# TapuinoMini.net
KiCad netlist of a schematic drawn in EAGLE
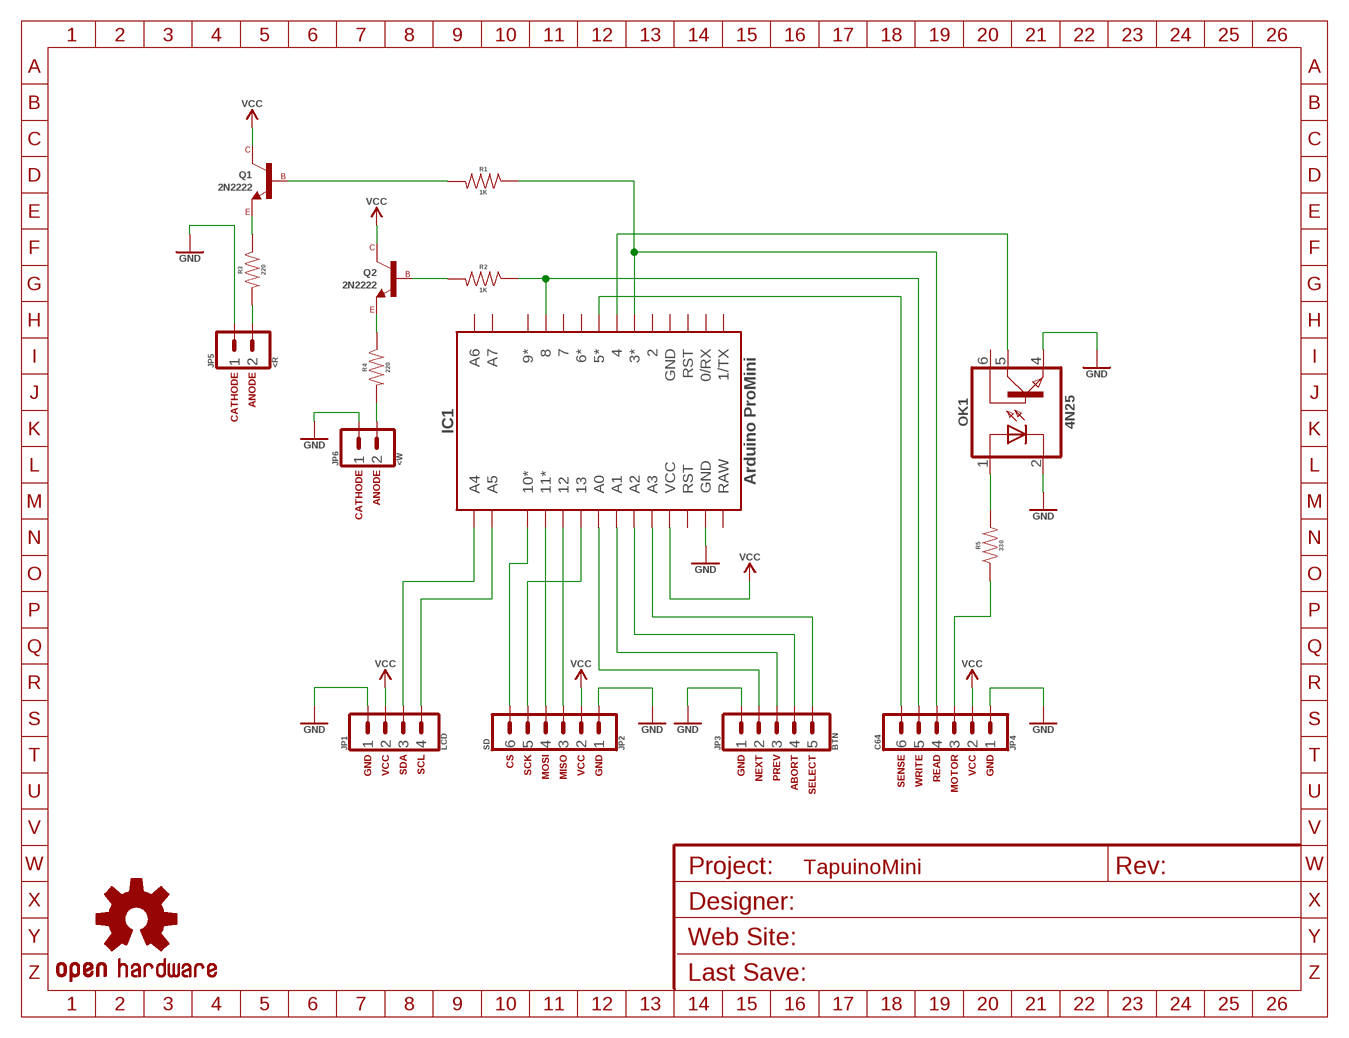
[diagram p0: schematic, sheet 1]

(export (version "E")
  (design (tool "Eeschema 10.0.6"))
  (components
    (comp (ref "IC1")
      (value "Arduino ProMini")
      (footprint "eagle-import:PROMINI_A")
      (libsource (lib "eagle-import") (part "PROMINI_A"))
    )
    (comp (ref "JP1")
      (value "LCD")
      (footprint "eagle-import:1X04_SQR")
      (libsource (lib "eagle-import") (part "1X04_SQR"))
    )
    (comp (ref "JP2")
      (value "SD")
      (footprint "eagle-import:1X06_SQR")
      (libsource (lib "eagle-import") (part "1X06_SQR"))
    )
    (comp (ref "JP3")
      (value "BTN")
      (footprint "eagle-import:1X05_SQR")
      (libsource (lib "eagle-import") (part "1X05_SQR"))
    )
    (comp (ref "JP4")
      (value "C64")
      (footprint "eagle-import:1X06_SQR")
      (libsource (lib "eagle-import") (part "1X06_SQR"))
    )
    (comp (ref "JP5")
      (value "<R")
      (footprint "eagle-import:1X02_SQR")
      (libsource (lib "eagle-import") (part "1X02_SQR"))
    )
    (comp (ref "JP6")
      (value "<W")
      (footprint "eagle-import:1X02_SQR")
      (libsource (lib "eagle-import") (part "1X02_SQR"))
    )
    (comp (ref "LOGO1")
      (value "OSHW-LOGOL")
      (footprint "eagle-import:OSHW-LOGO-L")
      (libsource (lib "eagle-import") (part "OSHW-LOGOL"))
    )
    (comp (ref "OK1")
      (value "4N25")
      (footprint "eagle-import:DIP06")
      (libsource (lib "eagle-import") (part "OPTO_6PIN_4NXX"))
    )
    (comp (ref "Q1")
      (value "2N2222")
      (footprint "eagle-import:TO-92")
      (libsource (lib "eagle-import") (part "TRANSISTOR_NPN_EBC"))
    )
    (comp (ref "Q2")
      (value "2N2222")
      (footprint "eagle-import:TO-92")
      (libsource (lib "eagle-import") (part "TRANSISTOR_NPN_EBC"))
    )
    (comp (ref "R1")
      (value "1K")
      (footprint "eagle-import:RESISTOR_PTH_0.3")
      (libsource (lib "eagle-import") (part "RESISTOR_PTH_0.3"))
    )
    (comp (ref "R2")
      (value "1K")
      (footprint "eagle-import:RESISTOR_PTH_0.3")
      (libsource (lib "eagle-import") (part "RESISTOR_PTH_0.3"))
    )
    (comp (ref "R3")
      (value "220")
      (footprint "eagle-import:RESISTOR_PTH_0.3")
      (libsource (lib "eagle-import") (part "RESISTOR_PTH_0.3"))
    )
    (comp (ref "R4")
      (value "220")
      (footprint "eagle-import:RESISTOR_PTH_0.3")
      (libsource (lib "eagle-import") (part "RESISTOR_PTH_0.3"))
    )
    (comp (ref "R5")
      (value "330")
      (footprint "eagle-import:RESISTOR_PTH_0.3")
      (libsource (lib "eagle-import") (part "RESISTOR_PTH_0.3"))
    )
  )
  (nets
    (net (code "1") (name "GND") (class "Default")
      (node (ref "IC1") (pin "GND@1") (pinfunction "GND_GND@1") (pintype "bidirectional"))
      (node (ref "JP1") (pin "1") (pinfunction "1_1") (pintype "passive"))
      (node (ref "JP2") (pin "1") (pinfunction "1_1") (pintype "passive"))
      (node (ref "JP3") (pin "1") (pinfunction "1_1") (pintype "passive"))
      (node (ref "JP4") (pin "1") (pinfunction "1_1") (pintype "passive"))
      (node (ref "JP5") (pin "1") (pinfunction "1_1") (pintype "passive"))
      (node (ref "JP6") (pin "1") (pinfunction "1_1") (pintype "passive"))
      (node (ref "OK1") (pin "2") (pinfunction "CATHODE_2") (pintype "passive"))
      (node (ref "OK1") (pin "4") (pinfunction "EMITTER_4") (pintype "passive"))
    )
    (net (code "2") (name "Net-(IC1-Pad3*)") (class "Default")
      (node (ref "IC1") (pin "3*") (pinfunction "3*_3*") (pintype "bidirectional"))
      (node (ref "JP4") (pin "4") (pinfunction "4_4") (pintype "passive"))
      (node (ref "R1") (pin "1") (pinfunction "1_1") (pintype "passive"))
    )
    (net (code "3") (name "Net-(IC1-Pad5*)") (class "Default")
      (node (ref "IC1") (pin "5*") (pinfunction "5*_5*") (pintype "bidirectional"))
      (node (ref "JP4") (pin "6") (pinfunction "6_6") (pintype "passive"))
    )
    (net (code "4") (name "Net-(IC1-Pad8)") (class "Default")
      (node (ref "IC1") (pin "8") (pinfunction "8_8") (pintype "bidirectional"))
      (node (ref "JP4") (pin "5") (pinfunction "5_5") (pintype "passive"))
      (node (ref "R2") (pin "1") (pinfunction "1_1") (pintype "passive"))
    )
    (net (code "5") (name "Net-(IC1-Pad10*)") (class "Default")
      (node (ref "IC1") (pin "10*") (pinfunction "10*_10*") (pintype "bidirectional"))
      (node (ref "JP2") (pin "6") (pinfunction "6_6") (pintype "passive"))
    )
    (net (code "6") (name "Net-(IC1-Pad11*)") (class "Default")
      (node (ref "IC1") (pin "11*") (pinfunction "11*_11*") (pintype "bidirectional"))
      (node (ref "JP2") (pin "4") (pinfunction "4_4") (pintype "passive"))
    )
    (net (code "7") (name "Net-(IC1-Pad12)") (class "Default")
      (node (ref "IC1") (pin "12") (pinfunction "12_12") (pintype "bidirectional"))
      (node (ref "JP2") (pin "3") (pinfunction "3_3") (pintype "passive"))
    )
    (net (code "8") (name "Net-(IC1-Pad13)") (class "Default")
      (node (ref "IC1") (pin "13") (pinfunction "13_13") (pintype "bidirectional"))
      (node (ref "JP2") (pin "5") (pinfunction "5_5") (pintype "passive"))
    )
    (net (code "9") (name "Net-(IC1-PadA0)") (class "Default")
      (node (ref "IC1") (pin "A0") (pinfunction "A0_A0") (pintype "bidirectional"))
      (node (ref "JP3") (pin "2") (pinfunction "2_2") (pintype "passive"))
    )
    (net (code "10") (name "Net-(IC1-PadA1)") (class "Default")
      (node (ref "IC1") (pin "A1") (pinfunction "A1_A1") (pintype "bidirectional"))
      (node (ref "JP3") (pin "3") (pinfunction "3_3") (pintype "passive"))
    )
    (net (code "11") (name "Net-(IC1-PadA2)") (class "Default")
      (node (ref "IC1") (pin "A2") (pinfunction "A2_A2") (pintype "bidirectional"))
      (node (ref "JP3") (pin "4") (pinfunction "4_4") (pintype "passive"))
    )
    (net (code "12") (name "Net-(IC1-PadA3)") (class "Default")
      (node (ref "IC1") (pin "A3") (pinfunction "A3_A3") (pintype "bidirectional"))
      (node (ref "JP3") (pin "5") (pinfunction "5_5") (pintype "passive"))
    )
    (net (code "13") (name "Net-(IC1-PadA4)") (class "Default")
      (node (ref "IC1") (pin "A4") (pinfunction "A4_A4") (pintype "bidirectional"))
      (node (ref "JP1") (pin "3") (pinfunction "3_3") (pintype "passive"))
    )
    (net (code "14") (name "Net-(IC1-PadA5)") (class "Default")
      (node (ref "IC1") (pin "A5") (pinfunction "A5_A5") (pintype "bidirectional"))
      (node (ref "JP1") (pin "4") (pinfunction "4_4") (pintype "passive"))
    )
    (net (code "15") (name "Net-(JP4-Pad3)") (class "Default")
      (node (ref "JP4") (pin "3") (pinfunction "3_3") (pintype "passive"))
      (node (ref "R5") (pin "1") (pinfunction "1_1") (pintype "passive"))
    )
    (net (code "16") (name "Net-(JP5-Pad2)") (class "Default")
      (node (ref "JP5") (pin "2") (pinfunction "2_2") (pintype "passive"))
      (node (ref "R3") (pin "2") (pinfunction "2_2") (pintype "passive"))
    )
    (net (code "17") (name "Net-(JP6-Pad2)") (class "Default")
      (node (ref "JP6") (pin "2") (pinfunction "2_2") (pintype "passive"))
      (node (ref "R4") (pin "2") (pinfunction "2_2") (pintype "passive"))
    )
    (net (code "18") (name "Net-(OK1-ANODE)") (class "Default")
      (node (ref "OK1") (pin "1") (pinfunction "ANODE_1") (pintype "passive"))
      (node (ref "R5") (pin "2") (pinfunction "2_2") (pintype "passive"))
    )
    (net (code "19") (name "Net-(OK1-COLLECTOR)") (class "Default")
      (node (ref "IC1") (pin "4") (pinfunction "4_4") (pintype "bidirectional"))
      (node (ref "OK1") (pin "5") (pinfunction "COLLECTOR_5") (pintype "passive"))
    )
    (net (code "20") (name "Net-(Q1-BASE)") (class "Default")
      (node (ref "Q1") (pin "2") (pinfunction "BASE_2") (pintype "passive"))
      (node (ref "R1") (pin "2") (pinfunction "2_2") (pintype "passive"))
    )
    (net (code "21") (name "Net-(Q1-EMITTER)") (class "Default")
      (node (ref "Q1") (pin "1") (pinfunction "EMITTER_1") (pintype "passive"))
      (node (ref "R3") (pin "1") (pinfunction "1_1") (pintype "passive"))
    )
    (net (code "22") (name "Net-(Q2-BASE)") (class "Default")
      (node (ref "Q2") (pin "2") (pinfunction "BASE_2") (pintype "passive"))
      (node (ref "R2") (pin "2") (pinfunction "2_2") (pintype "passive"))
    )
    (net (code "23") (name "Net-(Q2-EMITTER)") (class "Default")
      (node (ref "Q2") (pin "1") (pinfunction "EMITTER_1") (pintype "passive"))
      (node (ref "R4") (pin "1") (pinfunction "1_1") (pintype "passive"))
    )
    (net (code "24") (name "VCC") (class "Default")
      (node (ref "IC1") (pin "VCC") (pinfunction "VCC_VCC") (pintype "bidirectional"))
      (node (ref "JP1") (pin "2") (pinfunction "2_2") (pintype "passive"))
      (node (ref "JP2") (pin "2") (pinfunction "2_2") (pintype "passive"))
      (node (ref "JP4") (pin "2") (pinfunction "2_2") (pintype "passive"))
      (node (ref "Q1") (pin "3") (pinfunction "COLLECTOR_3") (pintype "passive"))
      (node (ref "Q2") (pin "3") (pinfunction "COLLECTOR_3") (pintype "passive"))
    )
    (net (code "25") (name "unconnected-(IC1-GND-PadGND@2)") (class "Default")
      (node (ref "IC1") (pin "GND@2") (pinfunction "GND_GND@2") (pintype "bidirectional"))
    )
    (net (code "26") (name "unconnected-(IC1-Pad0{slash}RX)") (class "Default")
      (node (ref "IC1") (pin "0/RX") (pinfunction "0/RX_0/RX") (pintype "bidirectional"))
    )
    (net (code "27") (name "unconnected-(IC1-Pad1{slash}TX)") (class "Default")
      (node (ref "IC1") (pin "1/TX") (pinfunction "1/TX_1/TX") (pintype "bidirectional"))
    )
    (net (code "28") (name "unconnected-(IC1-Pad2)") (class "Default")
      (node (ref "IC1") (pin "2") (pinfunction "2_2") (pintype "bidirectional"))
    )
    (net (code "29") (name "unconnected-(IC1-Pad6*)") (class "Default")
      (node (ref "IC1") (pin "6*") (pinfunction "6*_6*") (pintype "bidirectional"))
    )
    (net (code "30") (name "unconnected-(IC1-Pad7)") (class "Default")
      (node (ref "IC1") (pin "7") (pinfunction "7_7") (pintype "bidirectional"))
    )
    (net (code "31") (name "unconnected-(IC1-Pad9*)") (class "Default")
      (node (ref "IC1") (pin "9*") (pinfunction "9*_9*") (pintype "bidirectional"))
    )
    (net (code "32") (name "unconnected-(IC1-PadA6)") (class "Default")
      (node (ref "IC1") (pin "A6") (pinfunction "A6_A6") (pintype "bidirectional"))
    )
    (net (code "33") (name "unconnected-(IC1-PadA7)") (class "Default")
      (node (ref "IC1") (pin "A7") (pinfunction "A7_A7") (pintype "bidirectional"))
    )
    (net (code "34") (name "unconnected-(IC1-PadRAW)") (class "Default")
      (node (ref "IC1") (pin "RAW") (pinfunction "RAW_RAW") (pintype "bidirectional"))
    )
    (net (code "35") (name "unconnected-(IC1-RST-PadRST@1)") (class "Default")
      (node (ref "IC1") (pin "RST@1") (pinfunction "RST_RST@1") (pintype "bidirectional"))
    )
    (net (code "36") (name "unconnected-(IC1-RST-PadRST@2)") (class "Default")
      (node (ref "IC1") (pin "RST@2") (pinfunction "RST_RST@2") (pintype "bidirectional"))
    )
    (net (code "37") (name "unconnected-(OK1-BASE-Pad6)") (class "Default")
      (node (ref "OK1") (pin "6") (pinfunction "BASE_6") (pintype "passive"))
    )
  )
)
